# insect-bot.net
KiCad netlist of a schematic drawn in EAGLE
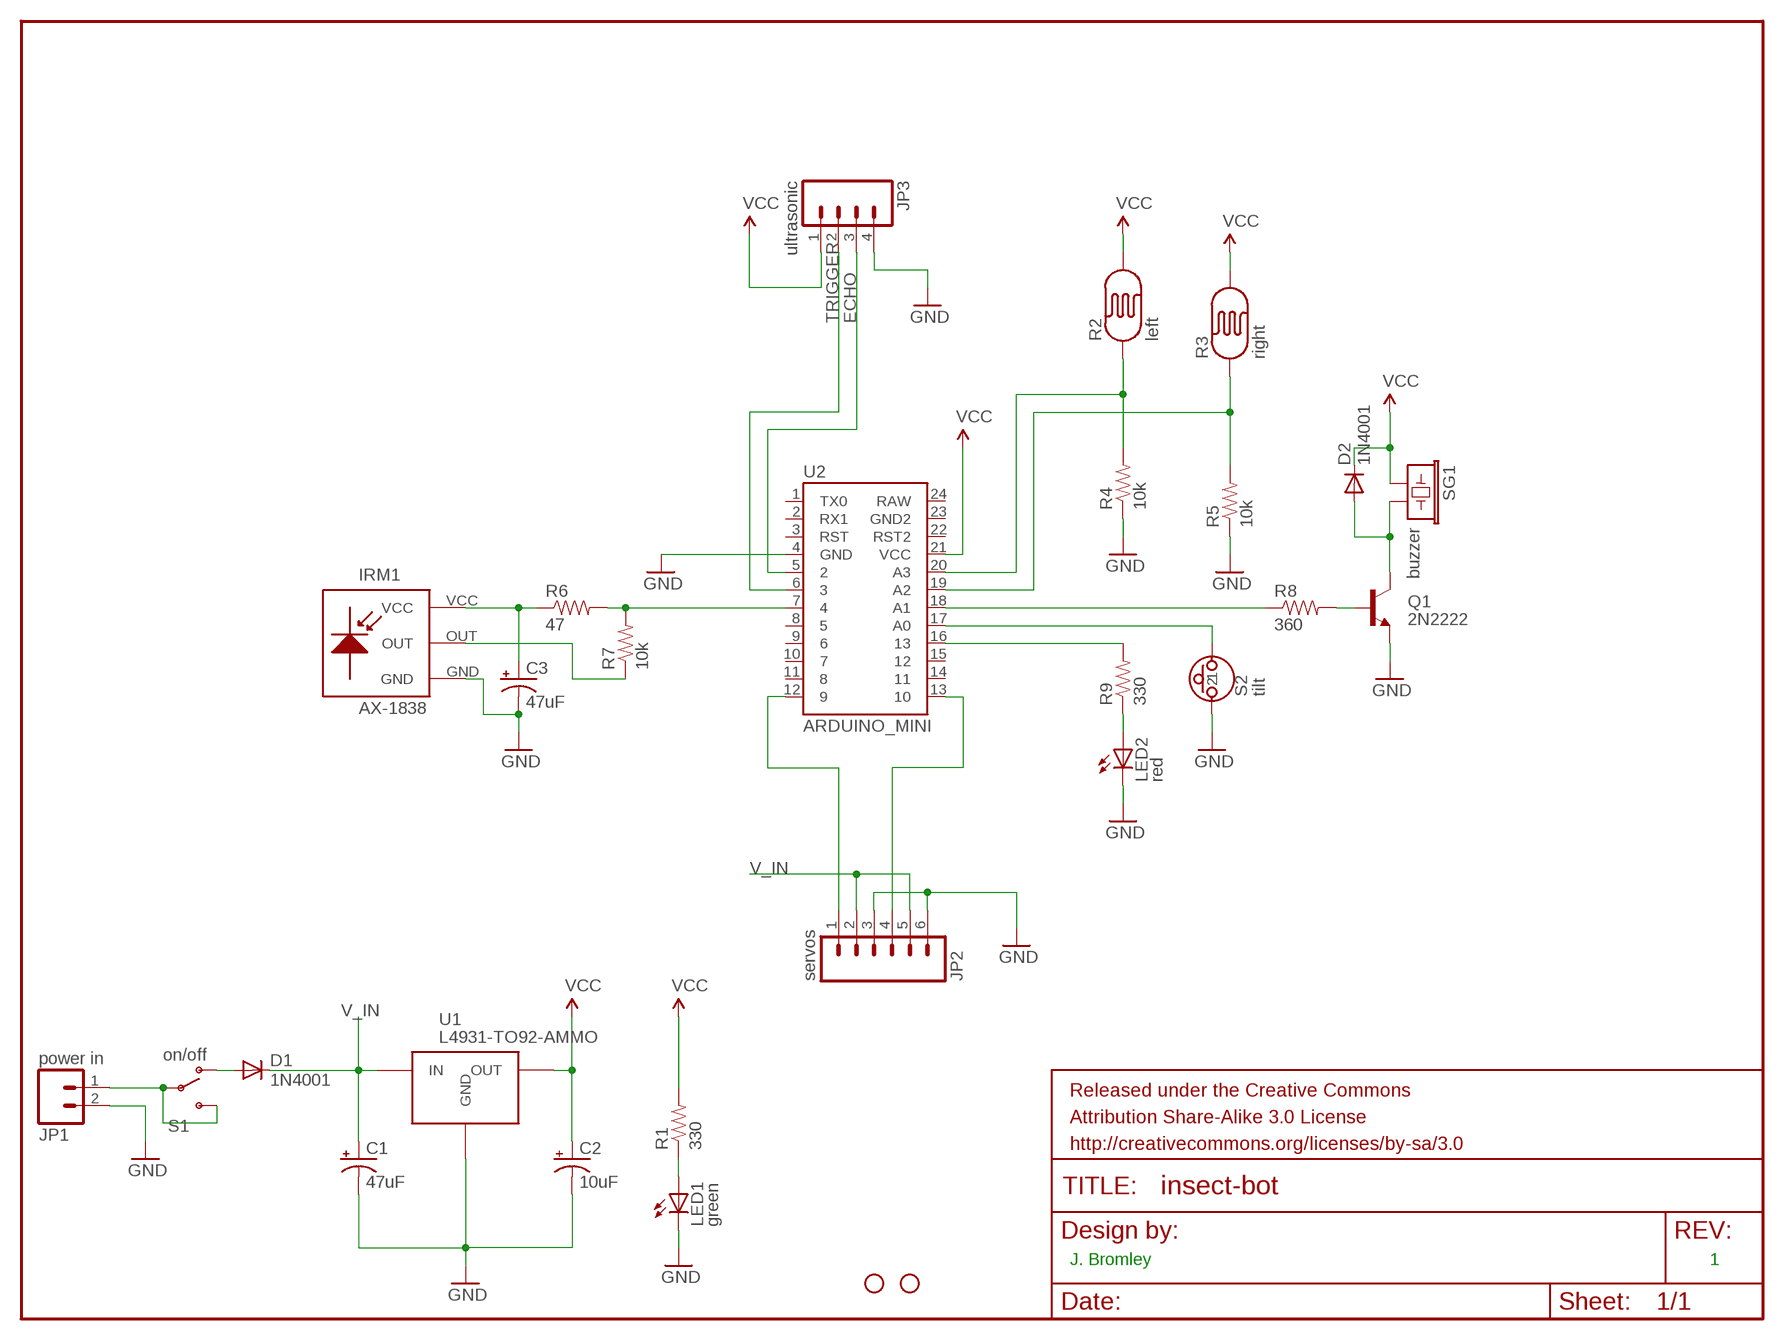
[diagram p0: schematic, sheet 1]

(export (version "E")
  (design (tool "Eeschema 10.0.6"))
  (components
    (comp (ref "C1")
      (value "47uF")
      (footprint "eagle-import:CPOL-RADIAL-10UF-25V")
      (libsource (lib "eagle-import") (part "CAP_POLPTH2"))
    )
    (comp (ref "C2")
      (value "10uF")
      (footprint "eagle-import:CPOL-RADIAL-10UF-25V")
      (libsource (lib "eagle-import") (part "CAP_POLPTH2"))
    )
    (comp (ref "C3")
      (value "47uF")
      (footprint "eagle-import:CPOL-RADIAL-100UF-25V")
      (libsource (lib "eagle-import") (part "CAP_POLPTH1"))
    )
    (comp (ref "D1")
      (value "1N4001")
      (footprint "eagle-import:DIODE-1N4001")
      (libsource (lib "eagle-import") (part "DIODEPTH"))
    )
    (comp (ref "D2")
      (value "1N4001")
      (footprint "eagle-import:DIODE-1N4001")
      (libsource (lib "eagle-import") (part "DIODEPTH"))
    )
    (comp (ref "IRM1")
      (value "AX-1838")
      (footprint "eagle-import:AX-1838")
      (libsource (lib "eagle-import") (part "AX-1838"))
    )
    (comp (ref "JP1")
      (value "power in")
      (footprint "eagle-import:1X02")
      (libsource (lib "eagle-import") (part "M02PTH"))
    )
    (comp (ref "JP2")
      (value "servos")
      (footprint "eagle-import:1X06")
      (libsource (lib "eagle-import") (part "M06SIP"))
    )
    (comp (ref "JP3")
      (value "ultrasonic")
      (footprint "eagle-import:1X04")
      (libsource (lib "eagle-import") (part "M04PTH"))
    )
    (comp (ref "JP4")
      (value "STAND-OFF")
      (footprint "eagle-import:STAND-OFF")
      (libsource (lib "eagle-import") (part "STAND-OFF"))
    )
    (comp (ref "JP5")
      (value "STAND-OFF")
      (footprint "eagle-import:STAND-OFF")
      (libsource (lib "eagle-import") (part "STAND-OFF"))
    )
    (comp (ref "LED1")
      (value "green")
      (footprint "eagle-import:LED3MM")
      (libsource (lib "eagle-import") (part "LED3MM"))
    )
    (comp (ref "LED2")
      (value "red")
      (footprint "eagle-import:LED3MM")
      (libsource (lib "eagle-import") (part "LED3MM"))
    )
    (comp (ref "Q1")
      (value "2N2222")
      (footprint "eagle-import:TO-92-AMMO")
      (libsource (lib "eagle-import") (part "TRANSISTOR_NPNTO-92-AMMO"))
    )
    (comp (ref "R1")
      (value "330")
      (footprint "eagle-import:AXIAL-0.3")
      (libsource (lib "eagle-import") (part "RESISTORAXIAL-0.3"))
    )
    (comp (ref "R2")
      (value "left")
      (footprint "eagle-import:PHOTOCELL")
      (libsource (lib "eagle-import") (part "PHOTOCELLPTH"))
    )
    (comp (ref "R3")
      (value "right")
      (footprint "eagle-import:PHOTOCELL")
      (libsource (lib "eagle-import") (part "PHOTOCELLPTH"))
    )
    (comp (ref "R4")
      (value "10k")
      (footprint "eagle-import:AXIAL-0.3")
      (libsource (lib "eagle-import") (part "RESISTORAXIAL-0.3"))
    )
    (comp (ref "R5")
      (value "10k")
      (footprint "eagle-import:AXIAL-0.3")
      (libsource (lib "eagle-import") (part "RESISTORAXIAL-0.3"))
    )
    (comp (ref "R6")
      (value "47")
      (footprint "eagle-import:AXIAL-0.3")
      (libsource (lib "eagle-import") (part "RESISTORAXIAL-0.3"))
    )
    (comp (ref "R7")
      (value "10k")
      (footprint "eagle-import:AXIAL-0.3")
      (libsource (lib "eagle-import") (part "RESISTORAXIAL-0.3"))
    )
    (comp (ref "R8")
      (value "360")
      (footprint "eagle-import:AXIAL-0.3")
      (libsource (lib "eagle-import") (part "RESISTORAXIAL-0.3"))
    )
    (comp (ref "R9")
      (value "330")
      (footprint "eagle-import:AXIAL-0.3")
      (libsource (lib "eagle-import") (part "RESISTORAXIAL-0.3"))
    )
    (comp (ref "S1")
      (value "on/off")
      (footprint "eagle-import:SWITCH-SPDT")
      (libsource (lib "eagle-import") (part "SWITCH-SPDTPTH"))
    )
    (comp (ref "S2")
      (value "tilt")
      (footprint "eagle-import:RADIAL-100")
      (libsource (lib "eagle-import") (part "TILTSWITCH"))
    )
    (comp (ref "SG1")
      (value "buzzer")
      (footprint "eagle-import:BUZZER-12MM")
      (libsource (lib "eagle-import") (part "BUZZERPTH"))
    )
    (comp (ref "U1")
      (value "L4931-TO92-AMMO")
      (footprint "eagle-import:TO-92-AMMO")
      (libsource (lib "eagle-import") (part "L4931-TO92-AMMO"))
    )
    (comp (ref "U2")
      (value "ARDUINO_MINI")
      (footprint "eagle-import:ARDUINO_MINI")
      (libsource (lib "eagle-import") (part "ARDUINO_MINI"))
    )
  )
  (nets
    (net (code "1") (name "/ECHO") (class "Default")
      (node (ref "JP3") (pin "3") (pinfunction "3_3") (pintype "passive"))
      (node (ref "U2") (pin "5") (pinfunction "2_5") (pintype "bidirectional"))
    )
    (net (code "2") (name "/TRIGGER") (class "Default")
      (node (ref "JP3") (pin "2") (pinfunction "2_2") (pintype "passive"))
      (node (ref "U2") (pin "6") (pinfunction "3_6") (pintype "bidirectional"))
    )
    (net (code "3") (name "/V_IN") (class "Default")
      (node (ref "C1") (pin "1") (pinfunction "+_1") (pintype "passive"))
      (node (ref "D1") (pin "C") (pinfunction "C_C") (pintype "passive"))
      (node (ref "JP2") (pin "2") (pinfunction "2_2") (pintype "passive"))
      (node (ref "JP2") (pin "5") (pinfunction "5_5") (pintype "passive"))
      (node (ref "U1") (pin "1") (pinfunction "IN_1") (pintype "power_in"))
    )
    (net (code "4") (name "GND") (class "Default")
      (node (ref "C1") (pin "2") (pinfunction "-_2") (pintype "passive"))
      (node (ref "C2") (pin "2") (pinfunction "-_2") (pintype "passive"))
      (node (ref "C3") (pin "2") (pinfunction "-_2") (pintype "passive"))
      (node (ref "IRM1") (pin "GND") (pinfunction "GND_GND") (pintype "power_in"))
      (node (ref "JP1") (pin "2") (pinfunction "2_2") (pintype "passive"))
      (node (ref "JP2") (pin "3") (pinfunction "3_3") (pintype "passive"))
      (node (ref "JP2") (pin "6") (pinfunction "6_6") (pintype "passive"))
      (node (ref "JP3") (pin "4") (pinfunction "4_4") (pintype "passive"))
      (node (ref "LED1") (pin "K") (pinfunction "C_K") (pintype "passive"))
      (node (ref "LED2") (pin "K") (pinfunction "C_K") (pintype "passive"))
      (node (ref "Q1") (pin "1") (pinfunction "E_1") (pintype "passive"))
      (node (ref "R4") (pin "P$1") (pinfunction "1_P$1") (pintype "passive"))
      (node (ref "R5") (pin "P$1") (pinfunction "1_P$1") (pintype "passive"))
      (node (ref "S2") (pin "1") (pinfunction "1_1") (pintype "passive"))
      (node (ref "U1") (pin "2") (pinfunction "GND_2") (pintype "power_in"))
      (node (ref "U2") (pin "4") (pinfunction "GND_4") (pintype "bidirectional"))
    )
    (net (code "5") (name "Net-(Q1-B)") (class "Default")
      (node (ref "Q1") (pin "2") (pinfunction "B_2") (pintype "passive"))
      (node (ref "R8") (pin "P$2") (pinfunction "2_P$2") (pintype "passive"))
    )
    (net (code "6") (name "Net-(Q1-C)") (class "Default")
      (node (ref "D2") (pin "A") (pinfunction "A_A") (pintype "passive"))
      (node (ref "Q1") (pin "3") (pinfunction "C_3") (pintype "passive"))
      (node (ref "SG1") (pin "-") (pinfunction "2_-") (pintype "passive"))
    )
    (net (code "7") (name "Net-(R1-1)") (class "Default")
      (node (ref "LED1") (pin "A") (pinfunction "A_A") (pintype "passive"))
      (node (ref "R1") (pin "P$1") (pinfunction "1_P$1") (pintype "passive"))
    )
    (net (code "8") (name "Net-(R2-P$1)") (class "Default")
      (node (ref "R2") (pin "1") (pinfunction "P$1_1") (pintype "bidirectional"))
      (node (ref "R4") (pin "P$2") (pinfunction "2_P$2") (pintype "passive"))
      (node (ref "U2") (pin "20") (pinfunction "A3_20") (pintype "bidirectional"))
    )
    (net (code "9") (name "Net-(R3-P$1)") (class "Default")
      (node (ref "R3") (pin "1") (pinfunction "P$1_1") (pintype "bidirectional"))
      (node (ref "R5") (pin "P$2") (pinfunction "2_P$2") (pintype "passive"))
      (node (ref "U2") (pin "19") (pinfunction "A2_19") (pintype "bidirectional"))
    )
    (net (code "10") (name "Net-(R6-2)") (class "Default")
      (node (ref "R6") (pin "P$2") (pinfunction "2_P$2") (pintype "passive"))
      (node (ref "R7") (pin "P$2") (pinfunction "2_P$2") (pintype "passive"))
      (node (ref "U2") (pin "7") (pinfunction "4_7") (pintype "bidirectional"))
    )
    (net (code "11") (name "Net-(R7-1)") (class "Default")
      (node (ref "IRM1") (pin "OUT") (pinfunction "OUT_OUT") (pintype "bidirectional"))
      (node (ref "R7") (pin "P$1") (pinfunction "1_P$1") (pintype "passive"))
    )
    (net (code "12") (name "Net-(R8-1)") (class "Default")
      (node (ref "R8") (pin "P$1") (pinfunction "1_P$1") (pintype "passive"))
      (node (ref "U2") (pin "18") (pinfunction "A1_18") (pintype "bidirectional"))
    )
    (net (code "13") (name "Net-(R9-1)") (class "Default")
      (node (ref "LED2") (pin "A") (pinfunction "A_A") (pintype "passive"))
      (node (ref "R9") (pin "P$1") (pinfunction "1_P$1") (pintype "passive"))
    )
    (net (code "14") (name "Net-(R9-2)") (class "Default")
      (node (ref "R9") (pin "P$2") (pinfunction "2_P$2") (pintype "passive"))
      (node (ref "U2") (pin "16") (pinfunction "13_16") (pintype "bidirectional"))
    )
    (net (code "15") (name "Net-(S1-O)") (class "Default")
      (node (ref "D1") (pin "A") (pinfunction "A_A") (pintype "passive"))
      (node (ref "S1") (pin "1") (pinfunction "O_1") (pintype "passive"))
    )
    (net (code "16") (name "Net-(S1-P)") (class "Default")
      (node (ref "JP1") (pin "1") (pinfunction "1_1") (pintype "passive"))
      (node (ref "S1") (pin "2") (pinfunction "P_2") (pintype "passive"))
      (node (ref "S1") (pin "3") (pinfunction "S_3") (pintype "passive"))
    )
    (net (code "17") (name "Net-(U2-9)") (class "Default")
      (node (ref "JP2") (pin "1") (pinfunction "1_1") (pintype "passive"))
      (node (ref "U2") (pin "12") (pinfunction "9_12") (pintype "bidirectional"))
    )
    (net (code "18") (name "Net-(U2-10)") (class "Default")
      (node (ref "JP2") (pin "4") (pinfunction "4_4") (pintype "passive"))
      (node (ref "U2") (pin "13") (pinfunction "10_13") (pintype "bidirectional"))
    )
    (net (code "19") (name "Net-(U2-A0)") (class "Default")
      (node (ref "S2") (pin "2") (pinfunction "2_2") (pintype "passive"))
      (node (ref "U2") (pin "17") (pinfunction "A0_17") (pintype "bidirectional"))
    )
    (net (code "20") (name "VCC") (class "Default")
      (node (ref "C2") (pin "1") (pinfunction "+_1") (pintype "passive"))
      (node (ref "C3") (pin "1") (pinfunction "+_1") (pintype "passive"))
      (node (ref "D2") (pin "C") (pinfunction "C_C") (pintype "passive"))
      (node (ref "IRM1") (pin "VCC") (pinfunction "VCC_VCC") (pintype "power_in"))
      (node (ref "JP3") (pin "1") (pinfunction "1_1") (pintype "passive"))
      (node (ref "R1") (pin "P$2") (pinfunction "2_P$2") (pintype "passive"))
      (node (ref "R2") (pin "2") (pinfunction "P$2_2") (pintype "bidirectional"))
      (node (ref "R3") (pin "2") (pinfunction "P$2_2") (pintype "bidirectional"))
      (node (ref "R6") (pin "P$1") (pinfunction "1_P$1") (pintype "passive"))
      (node (ref "SG1") (pin "+") (pinfunction "1_+") (pintype "passive"))
      (node (ref "U1") (pin "3") (pinfunction "OUT_3") (pintype "power_in"))
      (node (ref "U2") (pin "21") (pinfunction "VCC_21") (pintype "bidirectional"))
    )
    (net (code "21") (name "unconnected-(U2-5-Pad8)") (class "Default")
      (node (ref "U2") (pin "8") (pinfunction "5_8") (pintype "bidirectional"))
    )
    (net (code "22") (name "unconnected-(U2-6-Pad9)") (class "Default")
      (node (ref "U2") (pin "9") (pinfunction "6_9") (pintype "bidirectional"))
    )
    (net (code "23") (name "unconnected-(U2-7-Pad10)") (class "Default")
      (node (ref "U2") (pin "10") (pinfunction "7_10") (pintype "bidirectional"))
    )
    (net (code "24") (name "unconnected-(U2-8-Pad11)") (class "Default")
      (node (ref "U2") (pin "11") (pinfunction "8_11") (pintype "bidirectional"))
    )
    (net (code "25") (name "unconnected-(U2-11-Pad14)") (class "Default")
      (node (ref "U2") (pin "14") (pinfunction "11_14") (pintype "bidirectional"))
    )
    (net (code "26") (name "unconnected-(U2-12-Pad15)") (class "Default")
      (node (ref "U2") (pin "15") (pinfunction "12_15") (pintype "bidirectional"))
    )
    (net (code "27") (name "unconnected-(U2-GND2-Pad23)") (class "Default")
      (node (ref "U2") (pin "23") (pinfunction "GND2_23") (pintype "bidirectional"))
    )
    (net (code "28") (name "unconnected-(U2-RAW-Pad24)") (class "Default")
      (node (ref "U2") (pin "24") (pinfunction "RAW_24") (pintype "bidirectional"))
    )
    (net (code "29") (name "unconnected-(U2-RST-Pad3)") (class "Default")
      (node (ref "U2") (pin "3") (pinfunction "RST_3") (pintype "bidirectional"))
    )
    (net (code "30") (name "unconnected-(U2-RST2-Pad22)") (class "Default")
      (node (ref "U2") (pin "22") (pinfunction "RST2_22") (pintype "bidirectional"))
    )
    (net (code "31") (name "unconnected-(U2-RX1-Pad2)") (class "Default")
      (node (ref "U2") (pin "2") (pinfunction "RX1_2") (pintype "bidirectional"))
    )
    (net (code "32") (name "unconnected-(U2-TX0-Pad1)") (class "Default")
      (node (ref "U2") (pin "1") (pinfunction "TX0_1") (pintype "bidirectional"))
    )
  )
)
